# Super-Regenerative-FM-2.net
KiCad netlist of a schematic drawn in EAGLE
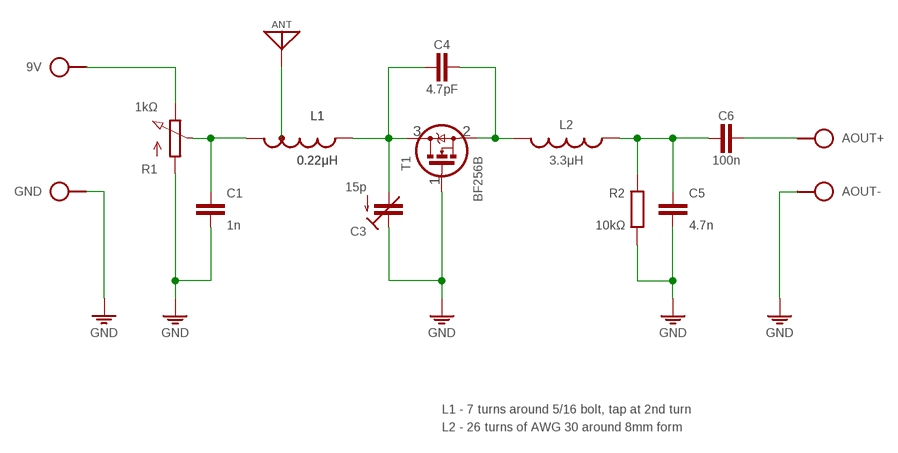
[diagram p0: schematic, sheet 1]

(export (version "E")
  (design (tool "Eeschema 10.0.6"))
  (components
    (comp (ref "9V")
      (value "SPAD")
      (footprint "eagle-import:SPAD")
      (libsource (lib "eagle-import") (part "SPAD"))
    )
    (comp (ref "ANT")
      (value "ANT")
      (footprint "eagle-import:SPAD")
      (libsource (lib "eagle-import") (part "ANT"))
    )
    (comp (ref "AOUT+")
      (value "SPAD")
      (footprint "eagle-import:SPAD")
      (libsource (lib "eagle-import") (part "SPAD"))
    )
    (comp (ref "AOUT-")
      (value "SPAD")
      (footprint "eagle-import:SPAD")
      (libsource (lib "eagle-import") (part "SPAD"))
    )
    (comp (ref "C1")
      (value "1n")
      (footprint "eagle-import:C050-020X036_V")
      (libsource (lib "eagle-import") (part "C050-020X036/V"))
    )
    (comp (ref "C3")
      (value "15p")
      (footprint "eagle-import:TRIM-2222-808")
      (libsource (lib "eagle-import") (part "C-TR-PH201272222-808-2PIN"))
    )
    (comp (ref "C4")
      (value "4.7pF")
      (footprint "eagle-import:C050-020X036")
      (libsource (lib "eagle-import") (part "C050-020X036"))
    )
    (comp (ref "C5")
      (value "4.7n")
      (footprint "eagle-import:C050-020X044")
      (libsource (lib "eagle-import") (part "C050-020X044"))
    )
    (comp (ref "C6")
      (value "100n")
      (footprint "eagle-import:C050-020X044")
      (libsource (lib "eagle-import") (part "C050-020X044"))
    )
    (comp (ref "GND")
      (value "SPAD")
      (footprint "eagle-import:SPAD")
      (libsource (lib "eagle-import") (part "SPAD"))
    )
    (comp (ref "L1")
      (value "0.22μH")
      (footprint "eagle-import:L-08_12-X-TAP1")
      (libsource (lib "eagle-import") (part "L-TAP1L-08/12-X-TAP1"))
    )
    (comp (ref "L2")
      (value "3.3μH")
      (footprint "eagle-import:L-BODY")
      (libsource (lib "eagle-import") (part "L-BODY"))
    )
    (comp (ref "R1")
      (value "1kΩ")
      (footprint "eagle-import:POT-V")
      (libsource (lib "eagle-import") (part "POT-V"))
    )
    (comp (ref "R2")
      (value "10kΩ")
      (footprint "eagle-import:0204_10")
      (libsource (lib "eagle-import") (part "R0204/10"))
    )
    (comp (ref "T1")
      (value "BF256B")
      (footprint "eagle-import:TO92")
      (libsource (lib "eagle-import") (part "BF256B"))
    )
  )
  (nets
    (net (code "1") (name "GND") (class "Default")
      (node (ref "AOUT-") (pin "1") (pinfunction "P$1_1") (pintype "bidirectional"))
      (node (ref "C1") (pin "2") (pinfunction "2_2") (pintype "passive"))
      (node (ref "C3") (pin "1") (pinfunction "E_1") (pintype "passive"))
      (node (ref "C5") (pin "2") (pinfunction "2_2") (pintype "passive"))
      (node (ref "GND") (pin "1") (pinfunction "P$1_1") (pintype "bidirectional"))
      (node (ref "R1") (pin "A") (pinfunction "A_A") (pintype "passive"))
      (node (ref "R2") (pin "1") (pinfunction "1_1") (pintype "passive"))
      (node (ref "T1") (pin "1") (pinfunction "G_1") (pintype "passive"))
    )
    (net (code "2") (name "Net-(9V-P$1)") (class "Default")
      (node (ref "9V") (pin "1") (pinfunction "P$1_1") (pintype "bidirectional"))
      (node (ref "R1") (pin "E") (pinfunction "E_E") (pintype "passive"))
    )
    (net (code "3") (name "Net-(AOUT+-P$1)") (class "Default")
      (node (ref "AOUT+") (pin "1") (pinfunction "P$1_1") (pintype "bidirectional"))
      (node (ref "C6") (pin "2") (pinfunction "2_2") (pintype "passive"))
    )
    (net (code "4") (name "Net-(C1-Pad1)") (class "Default")
      (node (ref "C1") (pin "1") (pinfunction "1_1") (pintype "passive"))
      (node (ref "L1") (pin "1") (pinfunction "1_1") (pintype "passive"))
      (node (ref "R1") (pin "S") (pinfunction "S_S") (pintype "passive"))
    )
    (net (code "5") (name "Net-(C3-A)") (class "Default")
      (node (ref "C3") (pin "2") (pinfunction "A_2") (pintype "passive"))
      (node (ref "C4") (pin "1") (pinfunction "1_1") (pintype "passive"))
      (node (ref "L1") (pin "2") (pinfunction "2_2") (pintype "passive"))
      (node (ref "T1") (pin "3") (pinfunction "D_3") (pintype "passive"))
    )
    (net (code "6") (name "Net-(L1-T)") (class "Default")
      (node (ref "ANT") (pin "1") (pinfunction "1_1") (pintype "output"))
      (node (ref "L1") (pin "3") (pinfunction "T_3") (pintype "passive"))
    )
    (net (code "7") (name "Net-(L2-1)") (class "Default")
      (node (ref "C5") (pin "1") (pinfunction "1_1") (pintype "passive"))
      (node (ref "C6") (pin "1") (pinfunction "1_1") (pintype "passive"))
      (node (ref "L2") (pin "2") (pinfunction "1_2") (pintype "passive"))
      (node (ref "R2") (pin "2") (pinfunction "2_2") (pintype "passive"))
    )
    (net (code "8") (name "Net-(L2-2)") (class "Default")
      (node (ref "C4") (pin "2") (pinfunction "2_2") (pintype "passive"))
      (node (ref "L2") (pin "3") (pinfunction "2_3") (pintype "passive"))
      (node (ref "T1") (pin "2") (pinfunction "S_2") (pintype "passive"))
    )
  )
)
